# 7seg_pcb.net
KiCad netlist of a schematic drawn in EAGLE
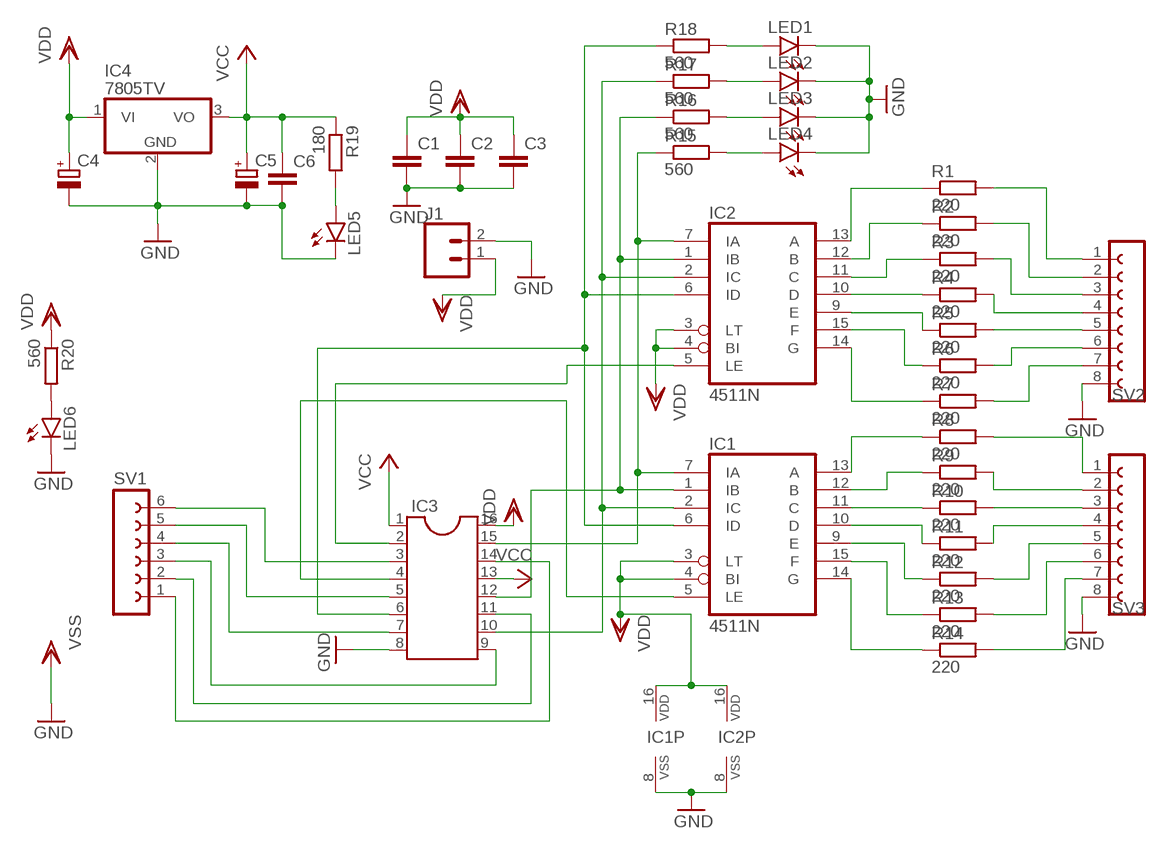
[diagram p0: schematic, sheet 1]

(export (version "E")
  (design (tool "Eeschema 10.0.6"))
  (components
    (comp (ref "C1")
      (value "C-EUC0805K")
      (footprint "eagle-import:C0805K")
      (libsource (lib "eagle-import") (part "C-EUC0805K"))
    )
    (comp (ref "C2")
      (value "C-EUC0805K")
      (footprint "eagle-import:C0805K")
      (libsource (lib "eagle-import") (part "C-EUC0805K"))
    )
    (comp (ref "C3")
      (value "C-EUC0805K")
      (footprint "eagle-import:C0805K")
      (libsource (lib "eagle-import") (part "C-EUC0805K"))
    )
    (comp (ref "C4")
      (value "CPOL-EUD")
      (footprint "eagle-import:PANASONIC_D")
      (libsource (lib "eagle-import") (part "CPOL-EUD"))
    )
    (comp (ref "C5")
      (value "CPOL-EUD")
      (footprint "eagle-import:PANASONIC_D")
      (libsource (lib "eagle-import") (part "CPOL-EUD"))
    )
    (comp (ref "C6")
      (value "C-EUC0805K")
      (footprint "eagle-import:C0805K")
      (libsource (lib "eagle-import") (part "C-EUC0805K"))
    )
    (comp (ref "IC1")
      (value "4511N")
      (footprint "eagle-import:DIL16")
      (libsource (lib "eagle-import") (part "4511N"))
    )
    (comp (ref "IC2")
      (value "4511N")
      (footprint "eagle-import:DIL16")
      (libsource (lib "eagle-import") (part "4511N"))
    )
    (comp (ref "IC3")
      (value "DIL16S")
      (footprint "eagle-import:SOCKET-16")
      (libsource (lib "eagle-import") (part "DIL16S"))
    )
    (comp (ref "IC4")
      (value "7805TV")
      (footprint "eagle-import:TO220V")
      (libsource (lib "eagle-import") (part "78TV05"))
    )
    (comp (ref "J1")
      (value "CONN_025MM")
      (footprint "eagle-import:SCREWTERMINAL-5MM-2")
      (libsource (lib "eagle-import") (part "CONN_025MM"))
    )
    (comp (ref "LED1")
      (value "LEDCHIPLED_0805")
      (footprint "eagle-import:CHIPLED_0805")
      (libsource (lib "eagle-import") (part "LEDCHIPLED_0805"))
    )
    (comp (ref "LED2")
      (value "LEDCHIPLED_0805")
      (footprint "eagle-import:CHIPLED_0805")
      (libsource (lib "eagle-import") (part "LEDCHIPLED_0805"))
    )
    (comp (ref "LED3")
      (value "LEDCHIPLED_0805")
      (footprint "eagle-import:CHIPLED_0805")
      (libsource (lib "eagle-import") (part "LEDCHIPLED_0805"))
    )
    (comp (ref "LED4")
      (value "LEDCHIPLED_0805")
      (footprint "eagle-import:CHIPLED_0805")
      (libsource (lib "eagle-import") (part "LEDCHIPLED_0805"))
    )
    (comp (ref "LED5")
      (value "LEDCHIPLED_0805")
      (footprint "eagle-import:CHIPLED_0805")
      (libsource (lib "eagle-import") (part "LEDCHIPLED_0805"))
    )
    (comp (ref "LED6")
      (value "LEDCHIPLED_0805")
      (footprint "eagle-import:CHIPLED_0805")
      (libsource (lib "eagle-import") (part "LEDCHIPLED_0805"))
    )
    (comp (ref "R1")
      (value "220")
      (footprint "eagle-import:R0805")
      (libsource (lib "eagle-import") (part "R-EU_R0805"))
    )
    (comp (ref "R2")
      (value "220")
      (footprint "eagle-import:R0805")
      (libsource (lib "eagle-import") (part "R-EU_R0805"))
    )
    (comp (ref "R3")
      (value "220")
      (footprint "eagle-import:R0805")
      (libsource (lib "eagle-import") (part "R-EU_R0805"))
    )
    (comp (ref "R4")
      (value "220")
      (footprint "eagle-import:R0805")
      (libsource (lib "eagle-import") (part "R-EU_R0805"))
    )
    (comp (ref "R5")
      (value "220")
      (footprint "eagle-import:R0805")
      (libsource (lib "eagle-import") (part "R-EU_R0805"))
    )
    (comp (ref "R6")
      (value "220")
      (footprint "eagle-import:R0805")
      (libsource (lib "eagle-import") (part "R-EU_R0805"))
    )
    (comp (ref "R7")
      (value "220")
      (footprint "eagle-import:R0805")
      (libsource (lib "eagle-import") (part "R-EU_R0805"))
    )
    (comp (ref "R8")
      (value "220")
      (footprint "eagle-import:R0805")
      (libsource (lib "eagle-import") (part "R-EU_R0805"))
    )
    (comp (ref "R9")
      (value "220")
      (footprint "eagle-import:R0805")
      (libsource (lib "eagle-import") (part "R-EU_R0805"))
    )
    (comp (ref "R10")
      (value "220")
      (footprint "eagle-import:R0805")
      (libsource (lib "eagle-import") (part "R-EU_R0805"))
    )
    (comp (ref "R11")
      (value "220")
      (footprint "eagle-import:R0805")
      (libsource (lib "eagle-import") (part "R-EU_R0805"))
    )
    (comp (ref "R12")
      (value "220")
      (footprint "eagle-import:R0805")
      (libsource (lib "eagle-import") (part "R-EU_R0805"))
    )
    (comp (ref "R13")
      (value "220")
      (footprint "eagle-import:R0805")
      (libsource (lib "eagle-import") (part "R-EU_R0805"))
    )
    (comp (ref "R14")
      (value "220")
      (footprint "eagle-import:R0805")
      (libsource (lib "eagle-import") (part "R-EU_R0805"))
    )
    (comp (ref "R15")
      (value "560")
      (footprint "eagle-import:R0805")
      (libsource (lib "eagle-import") (part "R-EU_R0805"))
    )
    (comp (ref "R16")
      (value "560")
      (footprint "eagle-import:R0805")
      (libsource (lib "eagle-import") (part "R-EU_R0805"))
    )
    (comp (ref "R17")
      (value "560")
      (footprint "eagle-import:R0805")
      (libsource (lib "eagle-import") (part "R-EU_R0805"))
    )
    (comp (ref "R18")
      (value "560")
      (footprint "eagle-import:R0805")
      (libsource (lib "eagle-import") (part "R-EU_R0805"))
    )
    (comp (ref "R19")
      (value "180")
      (footprint "eagle-import:R0805")
      (libsource (lib "eagle-import") (part "R-EU_R0805"))
    )
    (comp (ref "R20")
      (value "560")
      (footprint "eagle-import:R0805")
      (libsource (lib "eagle-import") (part "R-EU_R0805"))
    )
    (comp (ref "SV1")
      (value "FE06-1")
      (footprint "eagle-import:FE06")
      (libsource (lib "eagle-import") (part "FE06-1"))
    )
    (comp (ref "SV2")
      (value "FE08-1")
      (footprint "eagle-import:FE08")
      (libsource (lib "eagle-import") (part "FE08-1"))
    )
    (comp (ref "SV3")
      (value "FE08-1")
      (footprint "eagle-import:FE08")
      (libsource (lib "eagle-import") (part "FE08-1"))
    )
  )
  (nets
    (net (code "1") (name "GND") (class "Default")
      (node (ref "C1") (pin "2") (pinfunction "2_2") (pintype "passive"))
      (node (ref "C2") (pin "2") (pinfunction "2_2") (pintype "passive"))
      (node (ref "C3") (pin "2") (pinfunction "2_2") (pintype "passive"))
      (node (ref "C4") (pin "-") (pinfunction "-_-") (pintype "passive"))
      (node (ref "C5") (pin "-") (pinfunction "-_-") (pintype "passive"))
      (node (ref "C6") (pin "2") (pinfunction "2_2") (pintype "passive"))
      (node (ref "IC1") (pin "8") (pinfunction "VSS_8") (pintype "power_in"))
      (node (ref "IC2") (pin "8") (pinfunction "VSS_8") (pintype "power_in"))
      (node (ref "IC3") (pin "8") (pinfunction "8_8") (pintype "passive"))
      (node (ref "IC4") (pin "2") (pinfunction "GND_2") (pintype "passive"))
      (node (ref "J1") (pin "2") (pinfunction "2_2") (pintype "passive"))
      (node (ref "LED1") (pin "C") (pinfunction "C_C") (pintype "passive"))
      (node (ref "LED2") (pin "C") (pinfunction "C_C") (pintype "passive"))
      (node (ref "LED3") (pin "C") (pinfunction "C_C") (pintype "passive"))
      (node (ref "LED4") (pin "C") (pinfunction "C_C") (pintype "passive"))
      (node (ref "LED5") (pin "C") (pinfunction "C_C") (pintype "passive"))
      (node (ref "LED6") (pin "C") (pinfunction "C_C") (pintype "passive"))
      (node (ref "SV2") (pin "8") (pinfunction "8_8") (pintype "passive"))
      (node (ref "SV3") (pin "8") (pinfunction "8_8") (pintype "passive"))
    )
    (net (code "2") (name "Net-(IC1A-A)") (class "Default")
      (node (ref "IC1") (pin "13") (pinfunction "A_13") (pintype "output"))
      (node (ref "R8") (pin "1") (pinfunction "1_1") (pintype "passive"))
    )
    (net (code "3") (name "Net-(IC1A-B)") (class "Default")
      (node (ref "IC1") (pin "12") (pinfunction "B_12") (pintype "output"))
      (node (ref "R9") (pin "1") (pinfunction "1_1") (pintype "passive"))
    )
    (net (code "4") (name "Net-(IC1A-C)") (class "Default")
      (node (ref "IC1") (pin "11") (pinfunction "C_11") (pintype "output"))
      (node (ref "R10") (pin "1") (pinfunction "1_1") (pintype "passive"))
    )
    (net (code "5") (name "Net-(IC1A-D)") (class "Default")
      (node (ref "IC1") (pin "10") (pinfunction "D_10") (pintype "output"))
      (node (ref "R11") (pin "1") (pinfunction "1_1") (pintype "passive"))
    )
    (net (code "6") (name "Net-(IC1A-E)") (class "Default")
      (node (ref "IC1") (pin "9") (pinfunction "E_9") (pintype "output"))
      (node (ref "R12") (pin "1") (pinfunction "1_1") (pintype "passive"))
    )
    (net (code "7") (name "Net-(IC1A-F)") (class "Default")
      (node (ref "IC1") (pin "15") (pinfunction "F_15") (pintype "output"))
      (node (ref "R13") (pin "1") (pinfunction "1_1") (pintype "passive"))
    )
    (net (code "8") (name "Net-(IC1A-G)") (class "Default")
      (node (ref "IC1") (pin "14") (pinfunction "G_14") (pintype "output"))
      (node (ref "R14") (pin "1") (pinfunction "1_1") (pintype "passive"))
    )
    (net (code "9") (name "Net-(IC1A-IA)") (class "Default")
      (node (ref "IC1") (pin "7") (pinfunction "IA_7") (pintype "input"))
      (node (ref "IC2") (pin "7") (pinfunction "IA_7") (pintype "input"))
      (node (ref "IC3") (pin "15") (pinfunction "15_15") (pintype "passive"))
      (node (ref "R15") (pin "1") (pinfunction "1_1") (pintype "passive"))
    )
    (net (code "10") (name "Net-(IC1A-IB)") (class "Default")
      (node (ref "IC1") (pin "1") (pinfunction "IB_1") (pintype "input"))
      (node (ref "IC2") (pin "1") (pinfunction "IB_1") (pintype "input"))
      (node (ref "IC3") (pin "12") (pinfunction "12_12") (pintype "passive"))
      (node (ref "R16") (pin "1") (pinfunction "1_1") (pintype "passive"))
    )
    (net (code "11") (name "Net-(IC1A-IC)") (class "Default")
      (node (ref "IC1") (pin "2") (pinfunction "IC_2") (pintype "input"))
      (node (ref "IC2") (pin "2") (pinfunction "IC_2") (pintype "input"))
      (node (ref "IC3") (pin "10") (pinfunction "10_10") (pintype "passive"))
      (node (ref "R17") (pin "1") (pinfunction "1_1") (pintype "passive"))
    )
    (net (code "12") (name "Net-(IC1A-ID)") (class "Default")
      (node (ref "IC1") (pin "6") (pinfunction "ID_6") (pintype "input"))
      (node (ref "IC2") (pin "6") (pinfunction "ID_6") (pintype "input"))
      (node (ref "IC3") (pin "6") (pinfunction "6_6") (pintype "passive"))
      (node (ref "R18") (pin "1") (pinfunction "1_1") (pintype "passive"))
    )
    (net (code "13") (name "Net-(IC1A-LE)") (class "Default")
      (node (ref "IC1") (pin "5") (pinfunction "LE_5") (pintype "input"))
      (node (ref "IC3") (pin "4") (pinfunction "4_4") (pintype "passive"))
    )
    (net (code "14") (name "Net-(IC2A-A)") (class "Default")
      (node (ref "IC2") (pin "13") (pinfunction "A_13") (pintype "output"))
      (node (ref "R1") (pin "1") (pinfunction "1_1") (pintype "passive"))
    )
    (net (code "15") (name "Net-(IC2A-B)") (class "Default")
      (node (ref "IC2") (pin "12") (pinfunction "B_12") (pintype "output"))
      (node (ref "R2") (pin "1") (pinfunction "1_1") (pintype "passive"))
    )
    (net (code "16") (name "Net-(IC2A-C)") (class "Default")
      (node (ref "IC2") (pin "11") (pinfunction "C_11") (pintype "output"))
      (node (ref "R3") (pin "1") (pinfunction "1_1") (pintype "passive"))
    )
    (net (code "17") (name "Net-(IC2A-D)") (class "Default")
      (node (ref "IC2") (pin "10") (pinfunction "D_10") (pintype "output"))
      (node (ref "R4") (pin "1") (pinfunction "1_1") (pintype "passive"))
    )
    (net (code "18") (name "Net-(IC2A-E)") (class "Default")
      (node (ref "IC2") (pin "9") (pinfunction "E_9") (pintype "output"))
      (node (ref "R5") (pin "1") (pinfunction "1_1") (pintype "passive"))
    )
    (net (code "19") (name "Net-(IC2A-F)") (class "Default")
      (node (ref "IC2") (pin "15") (pinfunction "F_15") (pintype "output"))
      (node (ref "R6") (pin "1") (pinfunction "1_1") (pintype "passive"))
    )
    (net (code "20") (name "Net-(IC2A-G)") (class "Default")
      (node (ref "IC2") (pin "14") (pinfunction "G_14") (pintype "output"))
      (node (ref "R7") (pin "1") (pinfunction "1_1") (pintype "passive"))
    )
    (net (code "21") (name "Net-(IC2A-LE)") (class "Default")
      (node (ref "IC2") (pin "5") (pinfunction "LE_5") (pintype "input"))
      (node (ref "IC3") (pin "2") (pinfunction "2_2") (pintype "passive"))
    )
    (net (code "22") (name "Net-(IC3-Pad3)") (class "Default")
      (node (ref "IC3") (pin "3") (pinfunction "3_3") (pintype "passive"))
      (node (ref "SV1") (pin "6") (pinfunction "6_6") (pintype "passive"))
    )
    (net (code "23") (name "Net-(IC3-Pad5)") (class "Default")
      (node (ref "IC3") (pin "5") (pinfunction "5_5") (pintype "passive"))
      (node (ref "SV1") (pin "5") (pinfunction "5_5") (pintype "passive"))
    )
    (net (code "24") (name "Net-(IC3-Pad7)") (class "Default")
      (node (ref "IC3") (pin "7") (pinfunction "7_7") (pintype "passive"))
      (node (ref "SV1") (pin "4") (pinfunction "4_4") (pintype "passive"))
    )
    (net (code "25") (name "Net-(IC3-Pad9)") (class "Default")
      (node (ref "IC3") (pin "9") (pinfunction "9_9") (pintype "passive"))
      (node (ref "SV1") (pin "3") (pinfunction "3_3") (pintype "passive"))
    )
    (net (code "26") (name "Net-(IC3-Pad11)") (class "Default")
      (node (ref "IC3") (pin "11") (pinfunction "11_11") (pintype "passive"))
      (node (ref "SV1") (pin "2") (pinfunction "2_2") (pintype "passive"))
    )
    (net (code "27") (name "Net-(IC3-Pad14)") (class "Default")
      (node (ref "IC3") (pin "14") (pinfunction "14_14") (pintype "passive"))
      (node (ref "SV1") (pin "1") (pinfunction "1_1") (pintype "passive"))
    )
    (net (code "28") (name "Net-(LED1-PadA)") (class "Default")
      (node (ref "LED1") (pin "A") (pinfunction "A_A") (pintype "passive"))
      (node (ref "R18") (pin "2") (pinfunction "2_2") (pintype "passive"))
    )
    (net (code "29") (name "Net-(LED2-PadA)") (class "Default")
      (node (ref "LED2") (pin "A") (pinfunction "A_A") (pintype "passive"))
      (node (ref "R17") (pin "2") (pinfunction "2_2") (pintype "passive"))
    )
    (net (code "30") (name "Net-(LED3-PadA)") (class "Default")
      (node (ref "LED3") (pin "A") (pinfunction "A_A") (pintype "passive"))
      (node (ref "R16") (pin "2") (pinfunction "2_2") (pintype "passive"))
    )
    (net (code "31") (name "Net-(LED4-PadA)") (class "Default")
      (node (ref "LED4") (pin "A") (pinfunction "A_A") (pintype "passive"))
      (node (ref "R15") (pin "2") (pinfunction "2_2") (pintype "passive"))
    )
    (net (code "32") (name "Net-(LED5-PadA)") (class "Default")
      (node (ref "LED5") (pin "A") (pinfunction "A_A") (pintype "passive"))
      (node (ref "R19") (pin "2") (pinfunction "2_2") (pintype "passive"))
    )
    (net (code "33") (name "Net-(LED6-PadA)") (class "Default")
      (node (ref "LED6") (pin "A") (pinfunction "A_A") (pintype "passive"))
      (node (ref "R20") (pin "2") (pinfunction "2_2") (pintype "passive"))
    )
    (net (code "34") (name "Net-(R1-Pad2)") (class "Default")
      (node (ref "R1") (pin "2") (pinfunction "2_2") (pintype "passive"))
      (node (ref "SV2") (pin "1") (pinfunction "1_1") (pintype "passive"))
    )
    (net (code "35") (name "Net-(R2-Pad2)") (class "Default")
      (node (ref "R2") (pin "2") (pinfunction "2_2") (pintype "passive"))
      (node (ref "SV2") (pin "2") (pinfunction "2_2") (pintype "passive"))
    )
    (net (code "36") (name "Net-(R3-Pad2)") (class "Default")
      (node (ref "R3") (pin "2") (pinfunction "2_2") (pintype "passive"))
      (node (ref "SV2") (pin "3") (pinfunction "3_3") (pintype "passive"))
    )
    (net (code "37") (name "Net-(R4-Pad2)") (class "Default")
      (node (ref "R4") (pin "2") (pinfunction "2_2") (pintype "passive"))
      (node (ref "SV2") (pin "4") (pinfunction "4_4") (pintype "passive"))
    )
    (net (code "38") (name "Net-(R5-Pad2)") (class "Default")
      (node (ref "R5") (pin "2") (pinfunction "2_2") (pintype "passive"))
      (node (ref "SV2") (pin "5") (pinfunction "5_5") (pintype "passive"))
    )
    (net (code "39") (name "Net-(R6-Pad2)") (class "Default")
      (node (ref "R6") (pin "2") (pinfunction "2_2") (pintype "passive"))
      (node (ref "SV2") (pin "6") (pinfunction "6_6") (pintype "passive"))
    )
    (net (code "40") (name "Net-(R7-Pad2)") (class "Default")
      (node (ref "R7") (pin "2") (pinfunction "2_2") (pintype "passive"))
      (node (ref "SV2") (pin "7") (pinfunction "7_7") (pintype "passive"))
    )
    (net (code "41") (name "Net-(R8-Pad2)") (class "Default")
      (node (ref "R8") (pin "2") (pinfunction "2_2") (pintype "passive"))
      (node (ref "SV3") (pin "1") (pinfunction "1_1") (pintype "passive"))
    )
    (net (code "42") (name "Net-(R9-Pad2)") (class "Default")
      (node (ref "R9") (pin "2") (pinfunction "2_2") (pintype "passive"))
      (node (ref "SV3") (pin "2") (pinfunction "2_2") (pintype "passive"))
    )
    (net (code "43") (name "Net-(R10-Pad2)") (class "Default")
      (node (ref "R10") (pin "2") (pinfunction "2_2") (pintype "passive"))
      (node (ref "SV3") (pin "3") (pinfunction "3_3") (pintype "passive"))
    )
    (net (code "44") (name "Net-(R11-Pad2)") (class "Default")
      (node (ref "R11") (pin "2") (pinfunction "2_2") (pintype "passive"))
      (node (ref "SV3") (pin "4") (pinfunction "4_4") (pintype "passive"))
    )
    (net (code "45") (name "Net-(R12-Pad2)") (class "Default")
      (node (ref "R12") (pin "2") (pinfunction "2_2") (pintype "passive"))
      (node (ref "SV3") (pin "5") (pinfunction "5_5") (pintype "passive"))
    )
    (net (code "46") (name "Net-(R13-Pad2)") (class "Default")
      (node (ref "R13") (pin "2") (pinfunction "2_2") (pintype "passive"))
      (node (ref "SV3") (pin "6") (pinfunction "6_6") (pintype "passive"))
    )
    (net (code "47") (name "Net-(R14-Pad2)") (class "Default")
      (node (ref "R14") (pin "2") (pinfunction "2_2") (pintype "passive"))
      (node (ref "SV3") (pin "7") (pinfunction "7_7") (pintype "passive"))
    )
    (net (code "48") (name "VCC") (class "Default")
      (node (ref "C5") (pin "+") (pinfunction "+_+") (pintype "passive"))
      (node (ref "C6") (pin "1") (pinfunction "1_1") (pintype "passive"))
      (node (ref "IC3") (pin "1") (pinfunction "1_1") (pintype "passive"))
      (node (ref "IC3") (pin "13") (pinfunction "13_13") (pintype "passive"))
      (node (ref "IC4") (pin "3") (pinfunction "VO_3") (pintype "passive"))
      (node (ref "R19") (pin "1") (pinfunction "1_1") (pintype "passive"))
    )
    (net (code "49") (name "VDD") (class "Default")
      (node (ref "C1") (pin "1") (pinfunction "1_1") (pintype "passive"))
      (node (ref "C2") (pin "1") (pinfunction "1_1") (pintype "passive"))
      (node (ref "C3") (pin "1") (pinfunction "1_1") (pintype "passive"))
      (node (ref "C4") (pin "+") (pinfunction "+_+") (pintype "passive"))
      (node (ref "IC1") (pin "16") (pinfunction "VDD_16") (pintype "power_in"))
      (node (ref "IC1") (pin "3") (pinfunction "LT_3") (pintype "input"))
      (node (ref "IC1") (pin "4") (pinfunction "BI_4") (pintype "input"))
      (node (ref "IC2") (pin "16") (pinfunction "VDD_16") (pintype "power_in"))
      (node (ref "IC2") (pin "3") (pinfunction "LT_3") (pintype "input"))
      (node (ref "IC2") (pin "4") (pinfunction "BI_4") (pintype "input"))
      (node (ref "IC3") (pin "16") (pinfunction "16_16") (pintype "passive"))
      (node (ref "IC4") (pin "1") (pinfunction "VI_1") (pintype "input"))
      (node (ref "J1") (pin "1") (pinfunction "1_1") (pintype "passive"))
      (node (ref "R20") (pin "1") (pinfunction "1_1") (pintype "passive"))
    )
  )
)
